# MAIN_SPACER_1.net
KiCad netlist of a schematic drawn in Altium Designer
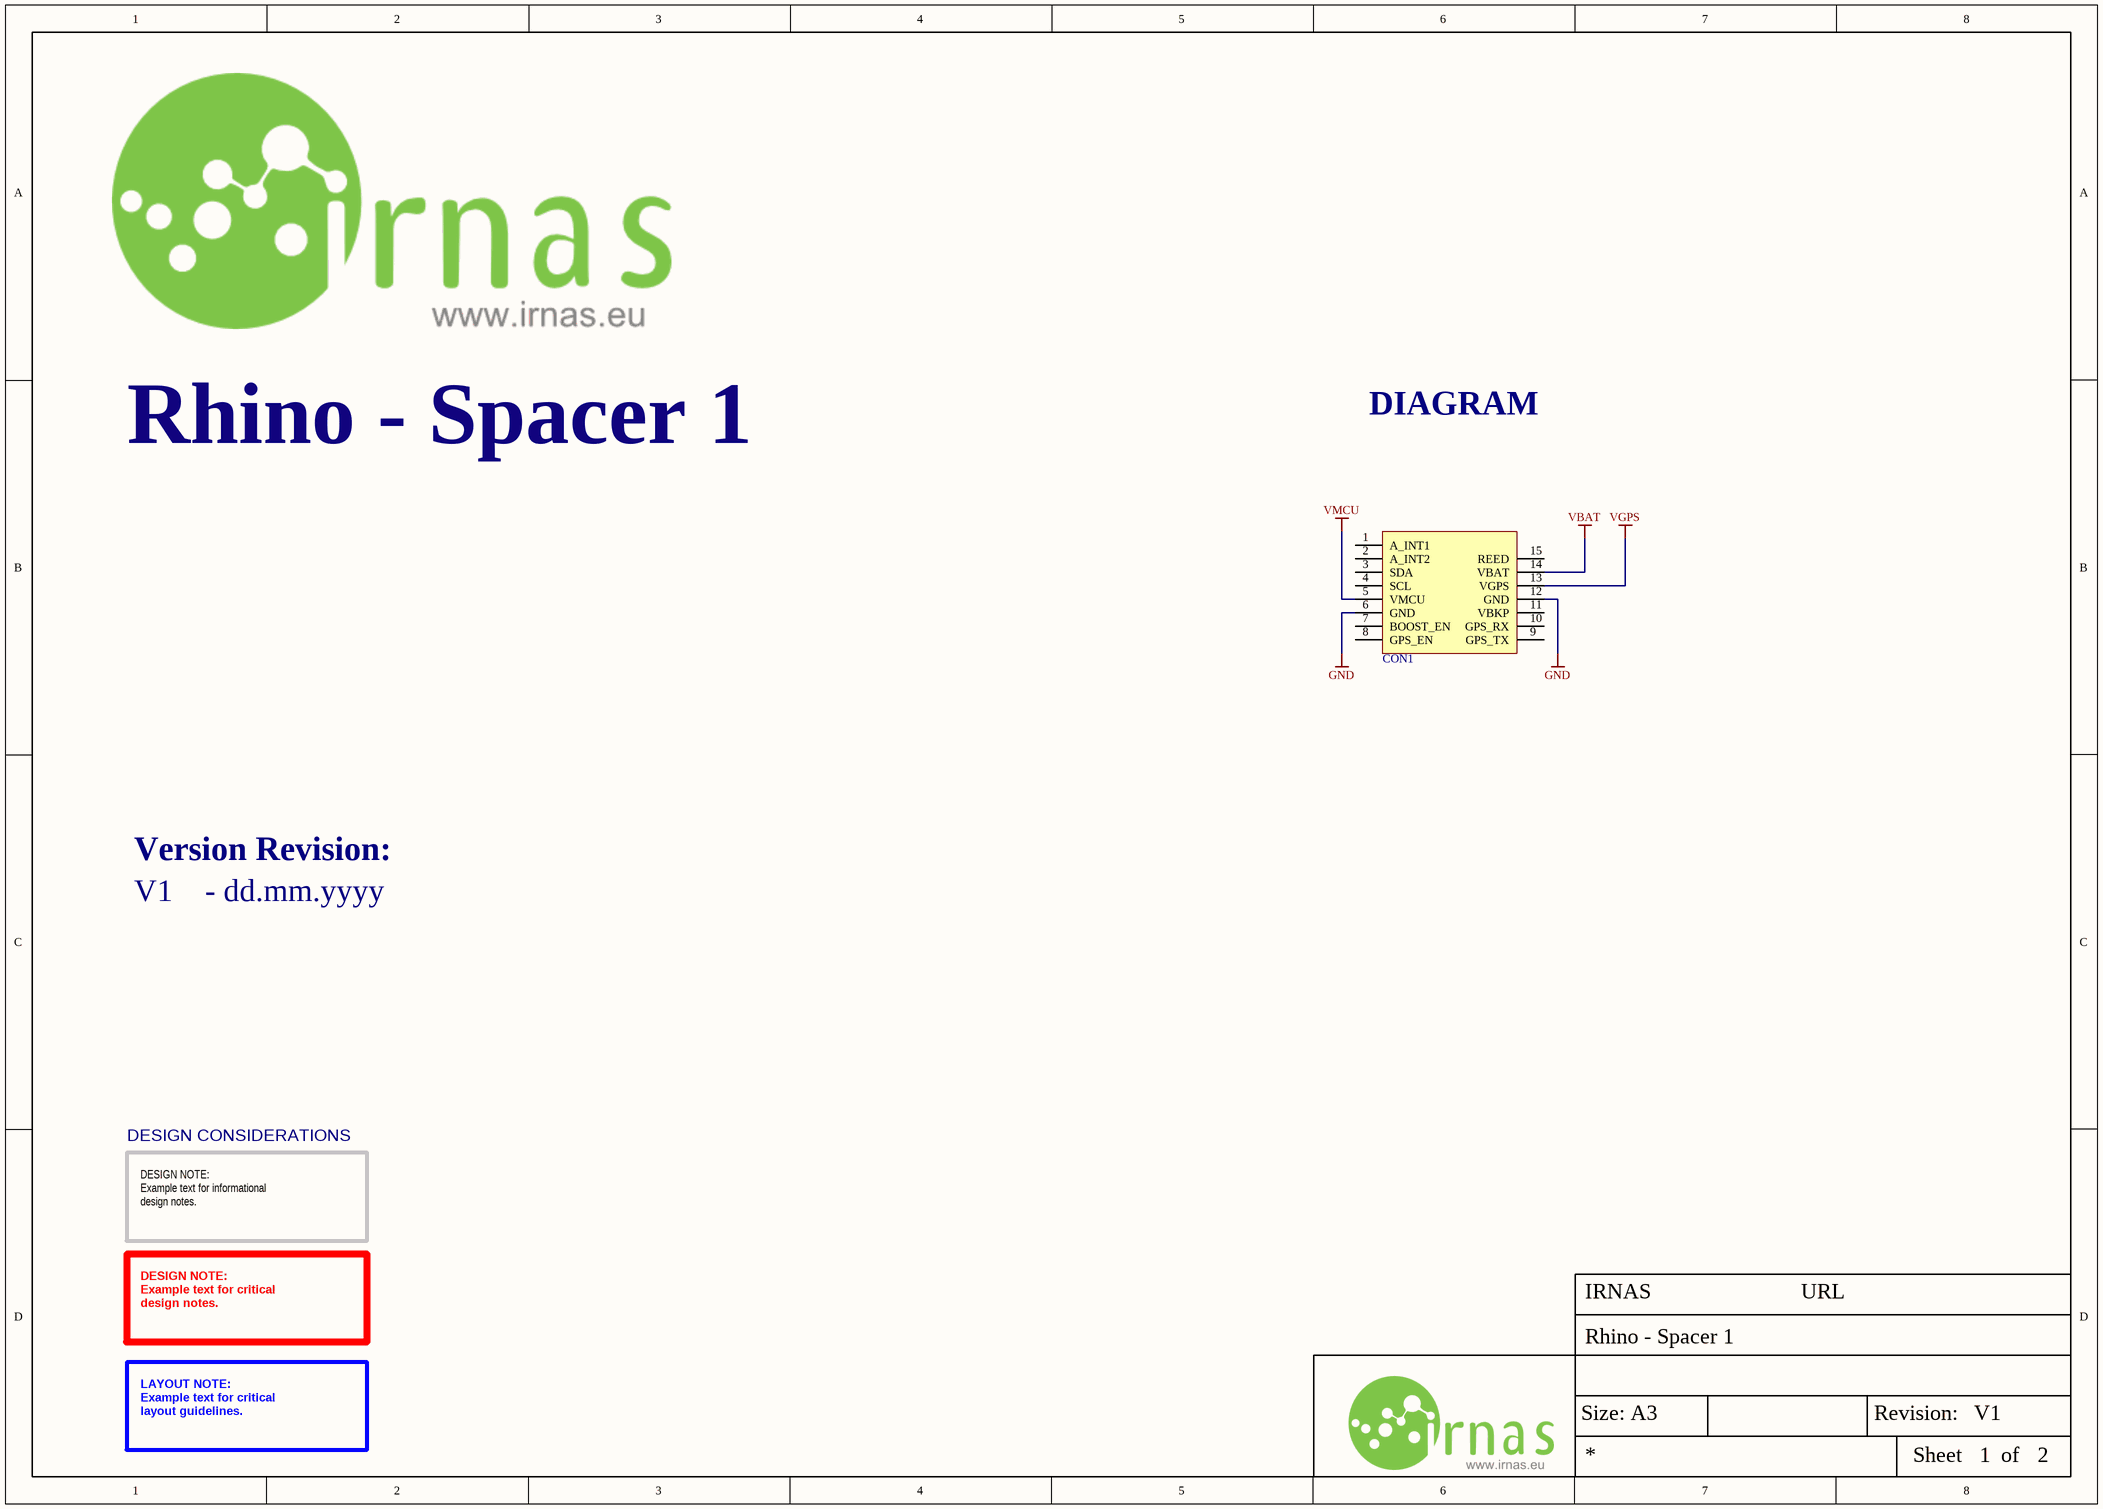
[diagram p0: MAIN_SPACER_1.SchDoc]

(export (version "E")
  (design (tool "Eeschema 10.0.6"))
  (components
    (comp (ref "CON1")
      (value "Between PCB connection")
      (footprint "SmartParks_Rhino")
      (libsource (lib "Connectors") (part "SmartParks_Rhino"))
    )
  )
  (nets
    (net (code "1") (name "GND") (class "Default")
      (node (ref "CON1") (pin "12") (pinfunction "GND_12") (pintype "passive"))
      (node (ref "CON1") (pin "6") (pinfunction "GND_6") (pintype "passive"))
    )
    (net (code "2") (name "VBAT") (class "Default")
      (node (ref "CON1") (pin "14") (pinfunction "VBAT_14") (pintype "passive"))
    )
    (net (code "3") (name "VGPS") (class "Default")
      (node (ref "CON1") (pin "13") (pinfunction "VGPS_13") (pintype "passive"))
    )
    (net (code "4") (name "VMCU") (class "Default")
      (node (ref "CON1") (pin "5") (pinfunction "VMCU_5") (pintype "passive"))
    )
    (net (code "5") (name "unconnected-(CON1-A_INT1-Pad1)") (class "Default")
      (node (ref "CON1") (pin "1") (pinfunction "A_INT1_1") (pintype "passive"))
    )
    (net (code "6") (name "unconnected-(CON1-A_INT2-Pad2)") (class "Default")
      (node (ref "CON1") (pin "2") (pinfunction "A_INT2_2") (pintype "passive"))
    )
    (net (code "7") (name "unconnected-(CON1-BOOST_EN-Pad7)") (class "Default")
      (node (ref "CON1") (pin "7") (pinfunction "BOOST_EN_7") (pintype "passive"))
    )
    (net (code "8") (name "unconnected-(CON1-GPS_EN-Pad8)") (class "Default")
      (node (ref "CON1") (pin "8") (pinfunction "GPS_EN_8") (pintype "passive"))
    )
    (net (code "9") (name "unconnected-(CON1-GPS_RX-Pad10)") (class "Default")
      (node (ref "CON1") (pin "10") (pinfunction "GPS_RX_10") (pintype "passive"))
    )
    (net (code "10") (name "unconnected-(CON1-GPS_TX-Pad9)") (class "Default")
      (node (ref "CON1") (pin "9") (pinfunction "GPS_TX_9") (pintype "passive"))
    )
    (net (code "11") (name "unconnected-(CON1-REED-Pad15)") (class "Default")
      (node (ref "CON1") (pin "15") (pinfunction "REED_15") (pintype "passive"))
    )
    (net (code "12") (name "unconnected-(CON1-SCL-Pad4)") (class "Default")
      (node (ref "CON1") (pin "4") (pinfunction "SCL_4") (pintype "passive"))
    )
    (net (code "13") (name "unconnected-(CON1-SDA-Pad3)") (class "Default")
      (node (ref "CON1") (pin "3") (pinfunction "SDA_3") (pintype "passive"))
    )
    (net (code "14") (name "unconnected-(CON1-VBKP-Pad11)") (class "Default")
      (node (ref "CON1") (pin "11") (pinfunction "VBKP_11") (pintype "passive"))
    )
  )
)
